# ESP32_LHCbit.net
KiCad netlist of a schematic drawn in Altium Designer
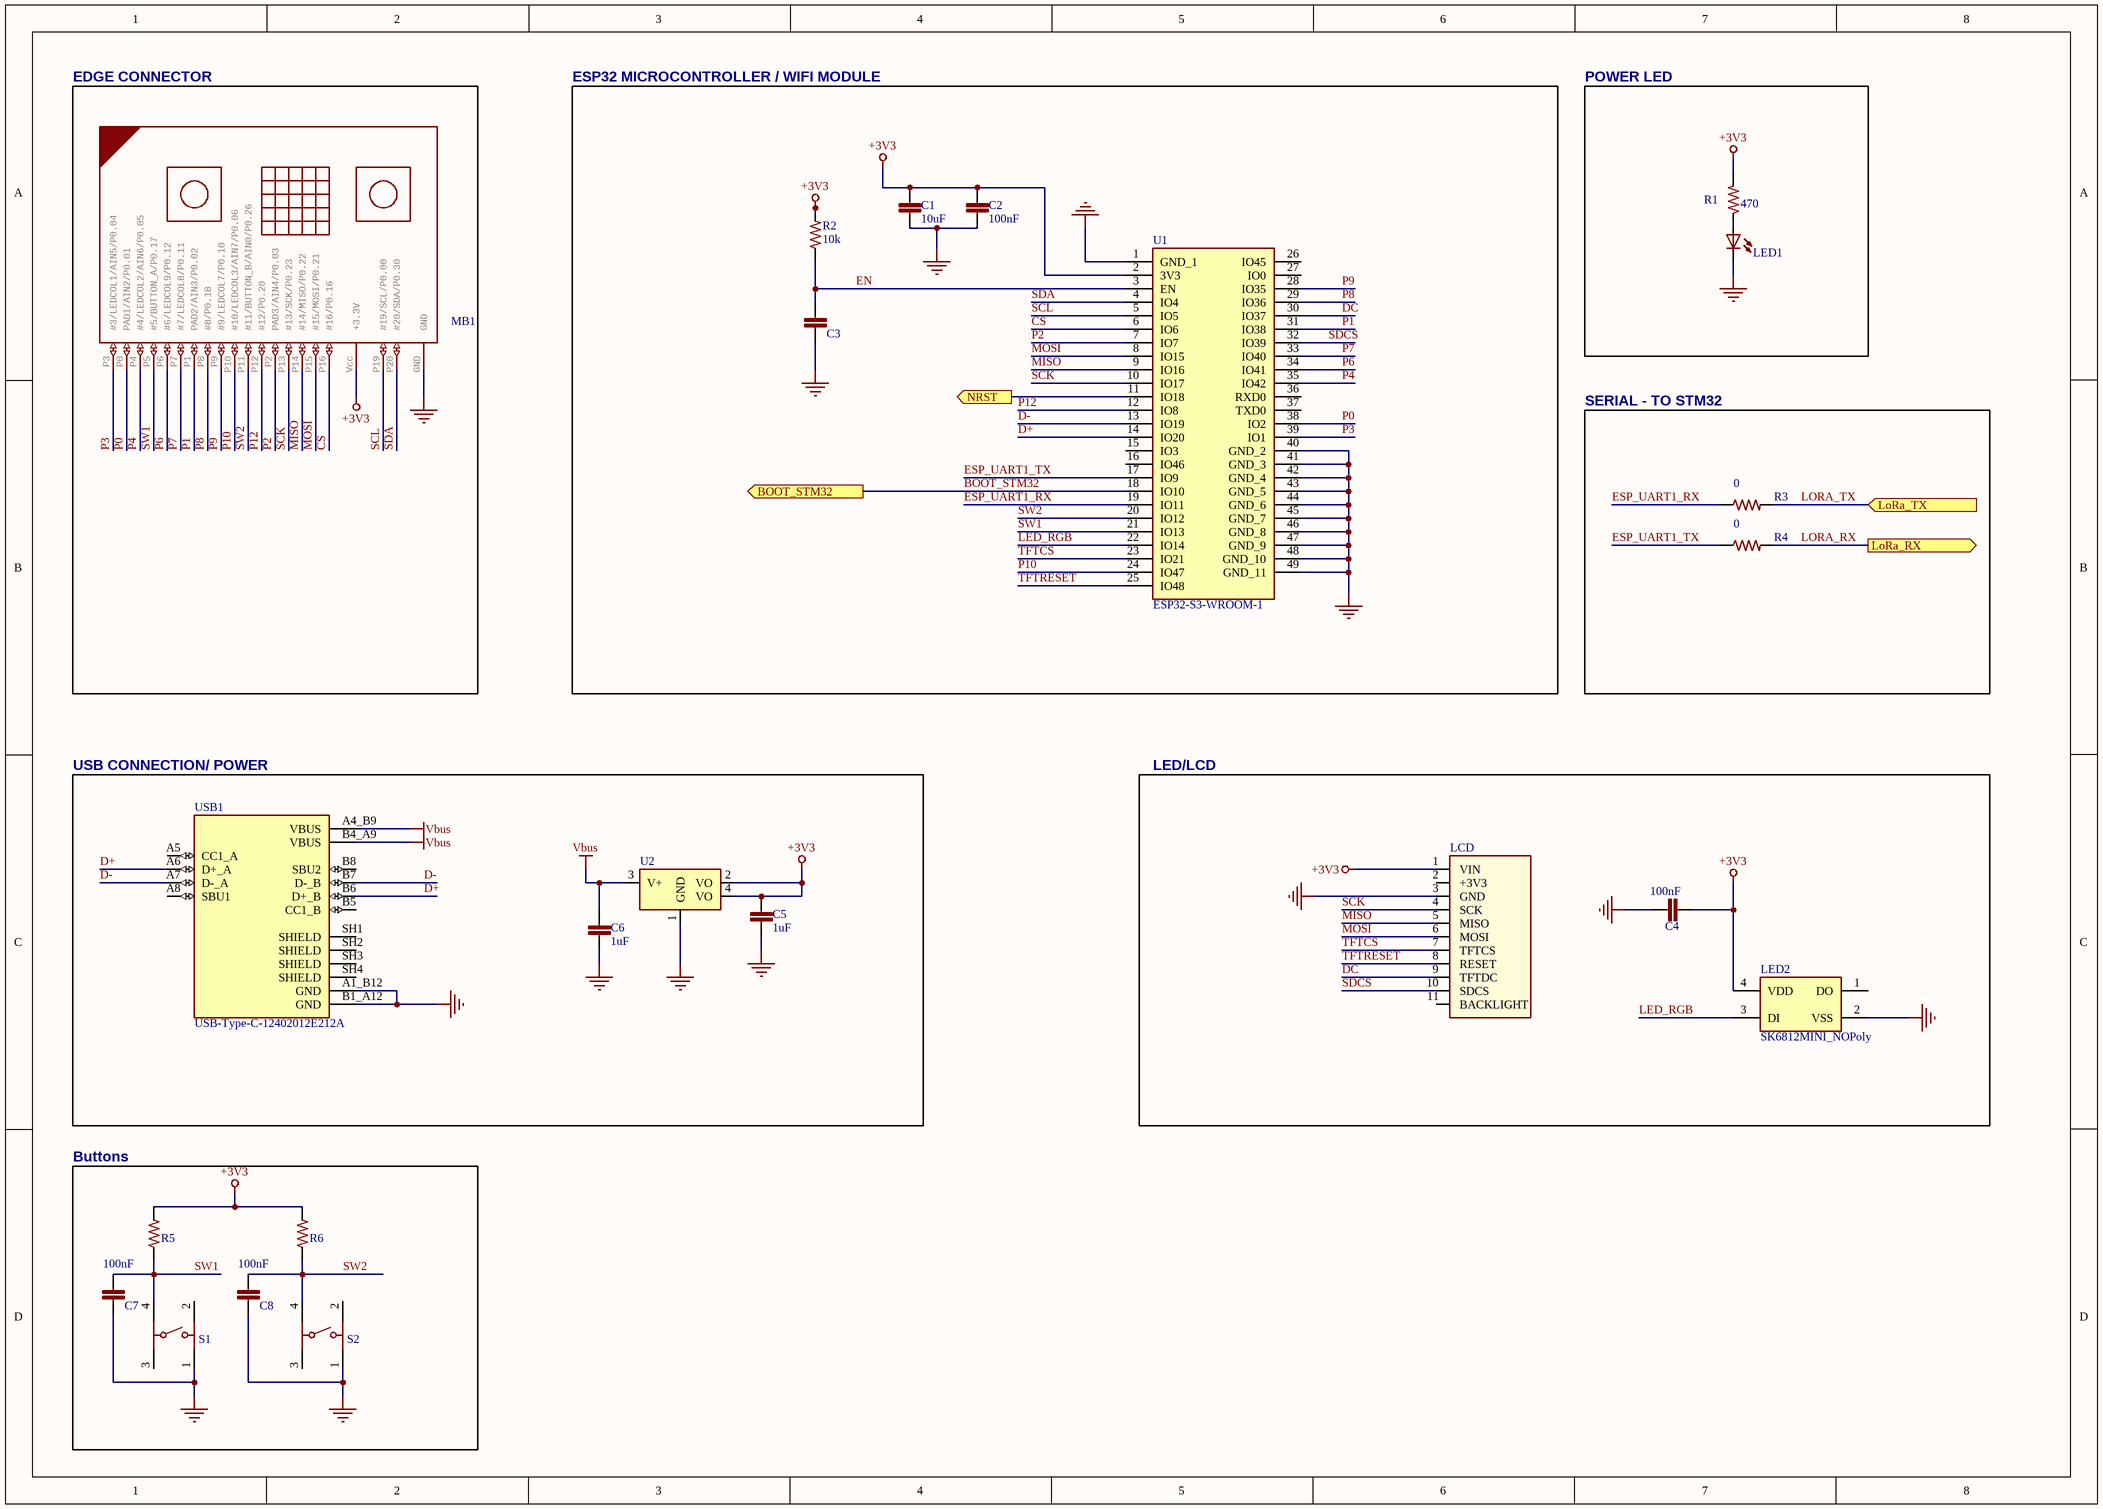
[diagram p0: ESP32_LHCbit.SchDoc]

(export (version "E")
  (design (tool "Eeschema 10.0.6"))
  (components
    (comp (ref "C1")
      (value "10uF")
      (footprint "C0603")
      (fields (field (name "PART NUMBER") "CL10A106KP8NNNC") (field (name "Comment") "C-EUC0603"))
      (libsource (lib "") (part "C-EUC0603_1"))
    )
    (comp (ref "C2")
      (value "100nF")
      (footprint "C0603")
      (fields (field (name "PART NUMBER") "CC0603KRX7R9BB104") (field (name "Comment") "C-EUC0603"))
      (libsource (lib "") (part "C-EUC0603_1"))
    )
    (comp (ref "C3")
      (value "C-EUC0402")
      (footprint "C0402")
      (fields (field (name "PART NUMBER") "C0402C104K8"))
      (libsource (lib "rcl") (part "C-EUC0402"))
    )
    (comp (ref "C4")
      (value "100nF")
      (footprint "C0402")
      (fields (field (name "PART NUMBER") "C0402C104K8") (field (name "Comment") "C-EUC0402"))
      (libsource (lib "") (part "C-EUC0402_1"))
    )
    (comp (ref "C5")
      (value "1uF")
      (footprint "C0603")
      (fields (field (name "PART NUMBER") "CL10A105KO8NNNC") (field (name "Comment") "C-EUC0603"))
      (libsource (lib "rcl") (part "C-EUC0603"))
    )
    (comp (ref "C6")
      (value "1uF")
      (footprint "C0603")
      (fields (field (name "PART NUMBER") "CL10A105KO8NNNC") (field (name "Comment") "C-EUC0603"))
      (libsource (lib "rcl") (part "C-EUC0603"))
    )
    (comp (ref "C7")
      (value "100nF")
      (footprint "C0402")
      (fields (field (name "PART NUMBER") "C0402C104K8") (field (name "Comment") "C-EUC0402"))
      (libsource (lib "rcl") (part "C-EUC0402"))
    )
    (comp (ref "C8")
      (value "100nF")
      (footprint "C0402")
      (fields (field (name "PART NUMBER") "C0402C104K8") (field (name "Comment") "C-EUC0402"))
      (libsource (lib "rcl") (part "C-EUC0402"))
    )
    (comp (ref "LCD")
      (value "Adafruit 0.96\"  TFT LCD")
      (footprint "ADafruit 0.96 Display")
      (libsource (lib "TE") (part "Adafruit 0.96{dblquote}  TFT LCD"))
    )
    (comp (ref "LED1")
      (value "~")
      (footprint "CHIPLED_0805")
      (fields (field (name "PART NUMBER") "AP2012EC"))
      (libsource (lib "led") (part "LEDCHIPLED_0805"))
    )
    (comp (ref "LED2")
      (value "SK6812MINI_NOPoly")
      (footprint "WS2812BMINI_no_poly")
      (description "SMD RGB (WS2812/SK6812MINI) 3535")
      (fields (field (name "PART NUMBER") "SK6812MINI"))
      (libsource (lib "led") (part "SK6812MINI_NOPoly"))
    )
    (comp (ref "MB1")
      (value "MICRO:BIT_EDGE")
      (footprint "MICROBIT_EDGE")
      (libsource (lib "TE") (part "MICRO{colon}BIT_EDGE"))
    )
    (comp (ref "R1")
      (value "470")
      (footprint "R0603")
      (fields (field (name "PART NUMBER") "RC0603FR-07470RL") (field (name "Comment") "R-US_R0603"))
      (libsource (lib "rcl") (part "R-US_R0603"))
    )
    (comp (ref "R2")
      (value "10k")
      (footprint "R0402")
      (fields (field (name "PART NUMBER") "RC0402FR-0710KL") (field (name "Comment") "R-US_R0402"))
      (libsource (lib "rcl") (part "R-US_R0402"))
    )
    (comp (ref "R3")
      (value "0")
      (footprint "R0402")
      (fields (field (name "PART NUMBER") "PA0402-R-070RL") (field (name "Comment") "R-US_R0402"))
      (libsource (lib "rcl") (part "R-US_R0402"))
    )
    (comp (ref "R4")
      (value "0")
      (footprint "R0402")
      (fields (field (name "PART NUMBER") "PA0402-R-070RL") (field (name "Comment") "R-US_R0402"))
      (libsource (lib "rcl") (part "R-US_R0402"))
    )
    (comp (ref "R5")
      (value "R-US_R0402")
      (footprint "R0402")
      (fields (field (name "PART NUMBER") "RC0402FR-0710KL"))
      (libsource (lib "rcl") (part "R-US_R0402"))
    )
    (comp (ref "R6")
      (value "R-US_R0402")
      (footprint "R0402")
      (fields (field (name "PART NUMBER") "RC0402FR-0710KL"))
      (libsource (lib "rcl") (part "R-US_R0402"))
    )
    (comp (ref "S1")
      (value "DTSM-6")
      (footprint "4301x20438x6_6x6x4.3_DTSM-6")
      (description "WS-TASV 6x6mm Tact Switch, SMD version")
      (libsource (lib "Switches") (part "DTSM-6"))
    )
    (comp (ref "S2")
      (value "DTSM-6")
      (footprint "4301x20438x6_6x6x4.3_DTSM-6")
      (description "WS-TASV 6x6mm Tact Switch, SMD version")
      (libsource (lib "Switches") (part "DTSM-6"))
    )
    (comp (ref "U1")
      (value "ESP32-S3-WROOM-1")
      (footprint "ESP32S3WROOM1N16R2")
      (description "Integrated Circuit")
      (fields (field (name "PART NUMBER") "ESP32-S3-WROOM-1-N16R2"))
      (libsource (lib "TE") (part "ESP32-S3-WROOM-1"))
    )
    (comp (ref "U2")
      (value "NCP1117LP")
      (footprint "SOT223")
      (fields (field (name "PART NUMBER") "TLV1117LV33DCYR"))
      (libsource (lib "TE") (part "NCP1117LP"))
    )
    (comp (ref "USB1")
      (value "USB-Type-C-12402012E212A")
      (footprint "AMPHENOL_12402012E212A")
      (description "USB2.0, Type C")
      (fields (field (name "PART NUMBER") "TYPEC-304-ACP16"))
      (libsource (lib "TE") (part "USB-Type-C-12402012E212A"))
    )
  )
  (nets
    (net (code "1") (name "+3V3") (class "Default")
      (node (ref "C1") (pin "1") (pinfunction "1_1") (pintype "passive"))
      (node (ref "C2") (pin "1") (pinfunction "1_1") (pintype "passive"))
      (node (ref "C4") (pin "2") (pinfunction "2_2") (pintype "passive"))
      (node (ref "C5") (pin "1") (pinfunction "1_1") (pintype "passive"))
      (node (ref "LCD") (pin "1") (pinfunction "VIN_1") (pintype "power_in"))
      (node (ref "LED2") (pin "4") (pinfunction "VDD_4") (pintype "passive"))
      (node (ref "MB1") (pin "Vcc") (pinfunction "+3.3V_Vcc") (pintype "power_in"))
      (node (ref "R1") (pin "2") (pinfunction "2_2") (pintype "passive"))
      (node (ref "R2") (pin "2") (pinfunction "2_2") (pintype "passive"))
      (node (ref "R5") (pin "2") (pinfunction "2_2") (pintype "passive"))
      (node (ref "R6") (pin "2") (pinfunction "2_2") (pintype "passive"))
      (node (ref "U1") (pin "2") (pinfunction "3V3_2") (pintype "passive"))
      (node (ref "U2") (pin "2") (pinfunction "VO_2") (pintype "passive"))
      (node (ref "U2") (pin "4") (pinfunction "VO_4") (pintype "passive"))
    )
    (net (code "2") (name "/BOOT_STM32") (class "Default")
      (node (ref "U1") (pin "18") (pinfunction "IO10_18") (pintype "passive"))
    )
    (net (code "3") (name "/CS") (class "Default")
      (node (ref "MB1") (pin "P16") (pinfunction "#16/P0.16_P16") (pintype "bidirectional"))
      (node (ref "U1") (pin "6") (pinfunction "IO6_6") (pintype "passive"))
    )
    (net (code "4") (name "/D+") (class "Default")
      (node (ref "U1") (pin "14") (pinfunction "IO20_14") (pintype "passive"))
      (node (ref "USB1") (pin "A6") (pinfunction "D+_A_A6") (pintype "bidirectional"))
      (node (ref "USB1") (pin "B6") (pinfunction "D+_B_B6") (pintype "bidirectional"))
    )
    (net (code "5") (name "/D-") (class "Default")
      (node (ref "U1") (pin "13") (pinfunction "IO19_13") (pintype "passive"))
      (node (ref "USB1") (pin "A7") (pinfunction "D-_A_A7") (pintype "bidirectional"))
      (node (ref "USB1") (pin "B7") (pinfunction "D-_B_B7") (pintype "bidirectional"))
    )
    (net (code "6") (name "/DC") (class "Default")
      (node (ref "LCD") (pin "9") (pinfunction "TFTDC_9") (pintype "passive"))
      (node (ref "U1") (pin "30") (pinfunction "IO37_30") (pintype "passive"))
    )
    (net (code "7") (name "/EN") (class "Default")
      (node (ref "C3") (pin "1") (pinfunction "1_1") (pintype "passive"))
      (node (ref "R2") (pin "1") (pinfunction "1_1") (pintype "passive"))
      (node (ref "U1") (pin "3") (pinfunction "EN_3") (pintype "passive"))
    )
    (net (code "8") (name "/ESP_UART1_RX") (class "Default")
      (node (ref "R3") (pin "1") (pinfunction "1_1") (pintype "passive"))
      (node (ref "U1") (pin "19") (pinfunction "IO11_19") (pintype "passive"))
    )
    (net (code "9") (name "/ESP_UART1_TX") (class "Default")
      (node (ref "R4") (pin "1") (pinfunction "1_1") (pintype "passive"))
      (node (ref "U1") (pin "17") (pinfunction "IO9_17") (pintype "passive"))
    )
    (net (code "10") (name "/LED_RGB") (class "Default")
      (node (ref "LED2") (pin "3") (pinfunction "DI_3") (pintype "passive"))
      (node (ref "U1") (pin "22") (pinfunction "IO14_22") (pintype "passive"))
    )
    (net (code "11") (name "/LORA_RX") (class "Default")
      (node (ref "R4") (pin "2") (pinfunction "2_2") (pintype "passive"))
    )
    (net (code "12") (name "/LORA_TX") (class "Default")
      (node (ref "R3") (pin "2") (pinfunction "2_2") (pintype "passive"))
    )
    (net (code "13") (name "/MISO") (class "Default")
      (node (ref "LCD") (pin "5") (pinfunction "MISO_5") (pintype "passive"))
      (node (ref "MB1") (pin "P14") (pinfunction "#14/MISO/P0.22_P14") (pintype "bidirectional"))
      (node (ref "U1") (pin "9") (pinfunction "IO16_9") (pintype "passive"))
    )
    (net (code "14") (name "/MOSI") (class "Default")
      (node (ref "LCD") (pin "6") (pinfunction "MOSI_6") (pintype "passive"))
      (node (ref "MB1") (pin "P15") (pinfunction "#15/MOSI/P0.21_P15") (pintype "bidirectional"))
      (node (ref "U1") (pin "8") (pinfunction "IO15_8") (pintype "passive"))
    )
    (net (code "15") (name "/NRST") (class "Default")
      (node (ref "U1") (pin "11") (pinfunction "IO18_11") (pintype "passive"))
    )
    (net (code "16") (name "/P0") (class "Default")
      (node (ref "MB1") (pin "P0") (pinfunction "PAD1/AIN2/P0.01_P0") (pintype "bidirectional"))
      (node (ref "U1") (pin "38") (pinfunction "IO2_38") (pintype "passive"))
    )
    (net (code "17") (name "/P1") (class "Default")
      (node (ref "MB1") (pin "P1") (pinfunction "PAD2/AIN3/P0.02_P1") (pintype "bidirectional"))
      (node (ref "U1") (pin "31") (pinfunction "IO38_31") (pintype "passive"))
    )
    (net (code "18") (name "/P2") (class "Default")
      (node (ref "MB1") (pin "P2") (pinfunction "PAD3/AIN4/P0.03_P2") (pintype "bidirectional"))
      (node (ref "U1") (pin "7") (pinfunction "IO7_7") (pintype "passive"))
    )
    (net (code "19") (name "/P3") (class "Default")
      (node (ref "MB1") (pin "P3") (pinfunction "#3/LEDCOL1/AIN5/P0.04_P3") (pintype "bidirectional"))
      (node (ref "U1") (pin "39") (pinfunction "IO1_39") (pintype "passive"))
    )
    (net (code "20") (name "/P4") (class "Default")
      (node (ref "MB1") (pin "P4") (pinfunction "#4/LEDCOL2/AIN6/P0.05_P4") (pintype "bidirectional"))
      (node (ref "U1") (pin "35") (pinfunction "IO42_35") (pintype "passive"))
    )
    (net (code "21") (name "/P6") (class "Default")
      (node (ref "MB1") (pin "P6") (pinfunction "#6/LEDCOL9/P0.12_P6") (pintype "bidirectional"))
      (node (ref "U1") (pin "34") (pinfunction "IO41_34") (pintype "passive"))
    )
    (net (code "22") (name "/P7") (class "Default")
      (node (ref "MB1") (pin "P7") (pinfunction "#7/LEDCOL8/P0.11_P7") (pintype "bidirectional"))
      (node (ref "U1") (pin "33") (pinfunction "IO40_33") (pintype "passive"))
    )
    (net (code "23") (name "/P8") (class "Default")
      (node (ref "MB1") (pin "P8") (pinfunction "#8/P0.18_P8") (pintype "bidirectional"))
      (node (ref "U1") (pin "29") (pinfunction "IO36_29") (pintype "passive"))
    )
    (net (code "24") (name "/P9") (class "Default")
      (node (ref "MB1") (pin "P9") (pinfunction "#9/LEDCOL7/P0.10_P9") (pintype "bidirectional"))
      (node (ref "U1") (pin "28") (pinfunction "IO35_28") (pintype "passive"))
    )
    (net (code "25") (name "/P10") (class "Default")
      (node (ref "MB1") (pin "P10") (pinfunction "#10/LEDCOL3/AIN7/P0.06_P10") (pintype "bidirectional"))
      (node (ref "U1") (pin "24") (pinfunction "IO47_24") (pintype "passive"))
    )
    (net (code "26") (name "/P12") (class "Default")
      (node (ref "MB1") (pin "P12") (pinfunction "#12/P0.20_P12") (pintype "bidirectional"))
      (node (ref "U1") (pin "12") (pinfunction "IO8_12") (pintype "passive"))
    )
    (net (code "27") (name "/SCK") (class "Default")
      (node (ref "LCD") (pin "4") (pinfunction "SCK_4") (pintype "passive"))
      (node (ref "MB1") (pin "P13") (pinfunction "#13/SCK/P0.23_P13") (pintype "bidirectional"))
      (node (ref "U1") (pin "10") (pinfunction "IO17_10") (pintype "passive"))
    )
    (net (code "28") (name "/SCL") (class "Default")
      (node (ref "MB1") (pin "P19") (pinfunction "#19/SCL/P0.00_P19") (pintype "bidirectional"))
      (node (ref "U1") (pin "5") (pinfunction "IO5_5") (pintype "passive"))
    )
    (net (code "29") (name "/SDA") (class "Default")
      (node (ref "MB1") (pin "P20") (pinfunction "#20/SDA/P0.30_P20") (pintype "bidirectional"))
      (node (ref "U1") (pin "4") (pinfunction "IO4_4") (pintype "passive"))
    )
    (net (code "30") (name "/SDCS") (class "Default")
      (node (ref "LCD") (pin "10") (pinfunction "SDCS_10") (pintype "passive"))
      (node (ref "U1") (pin "32") (pinfunction "IO39_32") (pintype "passive"))
    )
    (net (code "31") (name "/SW1") (class "Default")
      (node (ref "C7") (pin "1") (pinfunction "1_1") (pintype "passive"))
      (node (ref "MB1") (pin "P5") (pinfunction "#5/BUTTON_A/P0.17_P5") (pintype "bidirectional"))
      (node (ref "R5") (pin "1") (pinfunction "1_1") (pintype "passive"))
      (node (ref "S1") (pin "4") (pinfunction "4_4") (pintype "passive"))
      (node (ref "U1") (pin "21") (pinfunction "IO13_21") (pintype "passive"))
    )
    (net (code "32") (name "/SW2") (class "Default")
      (node (ref "C8") (pin "1") (pinfunction "1_1") (pintype "passive"))
      (node (ref "MB1") (pin "P11") (pinfunction "#11/BUTTON_B/AIN0/P0.26_P11") (pintype "bidirectional"))
      (node (ref "R6") (pin "1") (pinfunction "1_1") (pintype "passive"))
      (node (ref "S2") (pin "4") (pinfunction "4_4") (pintype "passive"))
      (node (ref "U1") (pin "20") (pinfunction "IO12_20") (pintype "passive"))
    )
    (net (code "33") (name "/TFTCS") (class "Default")
      (node (ref "LCD") (pin "7") (pinfunction "TFTCS_7") (pintype "passive"))
      (node (ref "U1") (pin "23") (pinfunction "IO21_23") (pintype "passive"))
    )
    (net (code "34") (name "/TFTRESET") (class "Default")
      (node (ref "LCD") (pin "8") (pinfunction "RESET_8") (pintype "passive"))
      (node (ref "U1") (pin "25") (pinfunction "IO48_25") (pintype "passive"))
    )
    (net (code "35") (name "GND") (class "Default")
      (node (ref "C1") (pin "2") (pinfunction "2_2") (pintype "passive"))
      (node (ref "C2") (pin "2") (pinfunction "2_2") (pintype "passive"))
      (node (ref "C3") (pin "2") (pinfunction "2_2") (pintype "passive"))
      (node (ref "C4") (pin "1") (pinfunction "1_1") (pintype "passive"))
      (node (ref "C5") (pin "2") (pinfunction "2_2") (pintype "passive"))
      (node (ref "C6") (pin "2") (pinfunction "2_2") (pintype "passive"))
      (node (ref "C7") (pin "2") (pinfunction "2_2") (pintype "passive"))
      (node (ref "C8") (pin "2") (pinfunction "2_2") (pintype "passive"))
      (node (ref "LCD") (pin "3") (pinfunction "GND_3") (pintype "passive"))
      (node (ref "LED1") (pin "C") (pinfunction "C_C") (pintype "passive"))
      (node (ref "LED2") (pin "2") (pinfunction "VSS_2") (pintype "passive"))
      (node (ref "MB1") (pin "GND") (pinfunction "GND_GND") (pintype "power_in"))
      (node (ref "S1") (pin "1") (pinfunction "1_1") (pintype "passive"))
      (node (ref "S2") (pin "1") (pinfunction "1_1") (pintype "passive"))
      (node (ref "U1") (pin "1") (pinfunction "GND_1_1") (pintype "passive"))
      (node (ref "U1") (pin "40") (pinfunction "GND_2_40") (pintype "passive"))
      (node (ref "U1") (pin "41") (pinfunction "GND_3_41") (pintype "passive"))
      (node (ref "U1") (pin "42") (pinfunction "GND_4_42") (pintype "passive"))
      (node (ref "U1") (pin "43") (pinfunction "GND_5_43") (pintype "passive"))
      (node (ref "U1") (pin "44") (pinfunction "GND_6_44") (pintype "passive"))
      (node (ref "U1") (pin "45") (pinfunction "GND_7_45") (pintype "passive"))
      (node (ref "U1") (pin "46") (pinfunction "GND_8_46") (pintype "passive"))
      (node (ref "U1") (pin "47") (pinfunction "GND_9_47") (pintype "passive"))
      (node (ref "U1") (pin "48") (pinfunction "GND_10_48") (pintype "passive"))
      (node (ref "U1") (pin "49") (pinfunction "GND_11_49") (pintype "passive"))
      (node (ref "U2") (pin "1") (pinfunction "GND_1") (pintype "power_in"))
      (node (ref "USB1") (pin "A1_B12") (pinfunction "GND_A1_B12") (pintype "power_in"))
      (node (ref "USB1") (pin "B1_A12") (pinfunction "GND_B1_A12") (pintype "power_in"))
    )
    (net (code "36") (name "Net-(LED1-PadA)") (class "Default")
      (node (ref "LED1") (pin "A") (pinfunction "A_A") (pintype "passive"))
      (node (ref "R1") (pin "1") (pinfunction "1_1") (pintype "passive"))
    )
    (net (code "37") (name "Vbus") (class "Default")
      (node (ref "C6") (pin "1") (pinfunction "1_1") (pintype "passive"))
      (node (ref "U2") (pin "3") (pinfunction "V+_3") (pintype "power_in"))
      (node (ref "USB1") (pin "A4_B9") (pinfunction "VBUS_A4_B9") (pintype "power_in"))
      (node (ref "USB1") (pin "B4_A9") (pinfunction "VBUS_B4_A9") (pintype "power_in"))
    )
    (net (code "38") (name "unconnected-(LCD-+3V3-Pad2)") (class "Default")
      (node (ref "LCD") (pin "2") (pinfunction "+3V3_2") (pintype "power_in"))
    )
    (net (code "39") (name "unconnected-(LCD-BACKLIGHT-Pad11)") (class "Default")
      (node (ref "LCD") (pin "11") (pinfunction "BACKLIGHT_11") (pintype "passive"))
    )
    (net (code "40") (name "unconnected-(LED2-DO-Pad1)") (class "Default")
      (node (ref "LED2") (pin "1") (pinfunction "DO_1") (pintype "passive"))
    )
    (net (code "41") (name "unconnected-(S1-Pad2)") (class "Default")
      (node (ref "S1") (pin "2") (pinfunction "2_2") (pintype "passive"))
    )
    (net (code "42") (name "unconnected-(S1-Pad3)") (class "Default")
      (node (ref "S1") (pin "3") (pinfunction "3_3") (pintype "passive"))
    )
    (net (code "43") (name "unconnected-(S2-Pad2)") (class "Default")
      (node (ref "S2") (pin "2") (pinfunction "2_2") (pintype "passive"))
    )
    (net (code "44") (name "unconnected-(S2-Pad3)") (class "Default")
      (node (ref "S2") (pin "3") (pinfunction "3_3") (pintype "passive"))
    )
    (net (code "45") (name "unconnected-(U1-IO0-Pad27)") (class "Default")
      (node (ref "U1") (pin "27") (pinfunction "IO0_27") (pintype "passive"))
    )
    (net (code "46") (name "unconnected-(U1-IO3-Pad15)") (class "Default")
      (node (ref "U1") (pin "15") (pinfunction "IO3_15") (pintype "passive"))
    )
    (net (code "47") (name "unconnected-(U1-IO45-Pad26)") (class "Default")
      (node (ref "U1") (pin "26") (pinfunction "IO45_26") (pintype "passive"))
    )
    (net (code "48") (name "unconnected-(U1-IO46-Pad16)") (class "Default")
      (node (ref "U1") (pin "16") (pinfunction "IO46_16") (pintype "passive"))
    )
    (net (code "49") (name "unconnected-(U1-RXD0-Pad36)") (class "Default")
      (node (ref "U1") (pin "36") (pinfunction "RXD0_36") (pintype "passive"))
    )
    (net (code "50") (name "unconnected-(U1-TXD0-Pad37)") (class "Default")
      (node (ref "U1") (pin "37") (pinfunction "TXD0_37") (pintype "passive"))
    )
    (net (code "51") (name "unconnected-(USB1-CC1_A-PadA5)") (class "Default")
      (node (ref "USB1") (pin "A5") (pinfunction "CC1_A_A5") (pintype "bidirectional"))
    )
    (net (code "52") (name "unconnected-(USB1-CC1_B-PadB5)") (class "Default")
      (node (ref "USB1") (pin "B5") (pinfunction "CC1_B_B5") (pintype "bidirectional"))
    )
    (net (code "53") (name "unconnected-(USB1-SBU1-PadA8)") (class "Default")
      (node (ref "USB1") (pin "A8") (pinfunction "SBU1_A8") (pintype "bidirectional"))
    )
    (net (code "54") (name "unconnected-(USB1-SBU2-PadB8)") (class "Default")
      (node (ref "USB1") (pin "B8") (pinfunction "SBU2_B8") (pintype "bidirectional"))
    )
    (net (code "55") (name "unconnected-(USB1-SHIELD-PadSH1)") (class "Default")
      (node (ref "USB1") (pin "SH1") (pinfunction "SHIELD_SH1") (pintype "passive"))
    )
    (net (code "56") (name "unconnected-(USB1-SHIELD-PadSH2)") (class "Default")
      (node (ref "USB1") (pin "SH2") (pinfunction "SHIELD_SH2") (pintype "passive"))
    )
    (net (code "57") (name "unconnected-(USB1-SHIELD-PadSH3)") (class "Default")
      (node (ref "USB1") (pin "SH3") (pinfunction "SHIELD_SH3") (pintype "passive"))
    )
    (net (code "58") (name "unconnected-(USB1-SHIELD-PadSH4)") (class "Default")
      (node (ref "USB1") (pin "SH4") (pinfunction "SHIELD_SH4") (pintype "passive"))
    )
  )
)
